# 24V_Regulators.net
KiCad netlist of a schematic drawn in Altium Designer
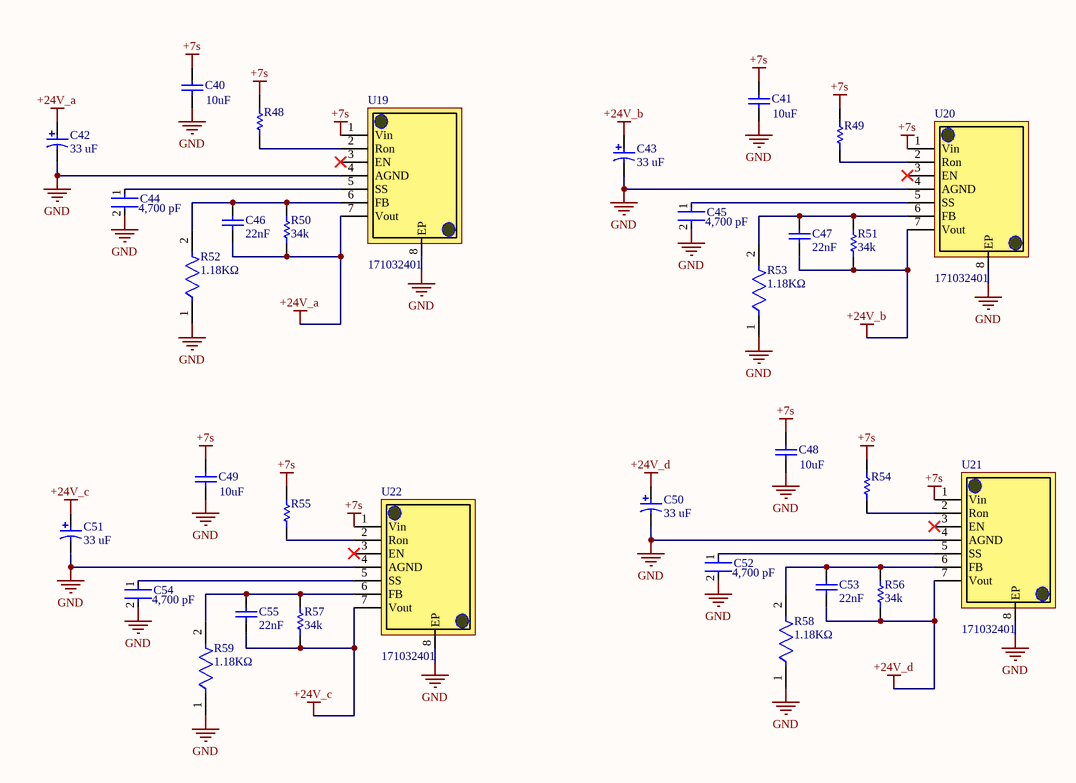
[diagram p0: 24V Regulators.SchDoc]

(export (version "E")
  (design (tool "Eeschema 10.0.6"))
  (components
    (comp (ref "C40")
      (value "10uF")
      (footprint "C1206")
      (description "Capacitor (Semiconductor SIM Model)")
      (fields (field (name "Comment") "Cap Semi") (field (name "PUBLISHER") "Altium Limited"))
      (libsource (lib "Miscellaneous Devices") (part "Cap Semi"))
    )
    (comp (ref "C41")
      (value "10uF")
      (footprint "C1206")
      (description "Capacitor (Semiconductor SIM Model)")
      (fields (field (name "Comment") "Cap Semi") (field (name "PUBLISHER") "Altium Limited"))
      (libsource (lib "Miscellaneous Devices") (part "Cap Semi"))
    )
    (comp (ref "C42")
      (value "UUD1V330MCL1GS")
      (footprint "NIC-CAPA2-6.3X5.8_V")
      (fields (field (name "MANUFACTURER") "Nichicon") (field (name "RATED CAPACITANCE") "33 uF"))
      (libsource (lib "Altium Content Vault") (part "NIC-CAP-P-2"))
    )
    (comp (ref "C43")
      (value "UUD1V330MCL1GS")
      (footprint "NIC-CAPA2-6.3X5.8_V")
      (fields (field (name "MANUFACTURER") "Nichicon") (field (name "RATED CAPACITANCE") "33 uF"))
      (libsource (lib "Altium Content Vault") (part "NIC-CAP-P-2"))
    )
    (comp (ref "C44")
      (value "C0805C472K5RACTU")
      (footprint "FP-C0805C-DN-MFG")
      (description "CAP CER 4700PF 50V X7R 0805")
      (fields
        (field (name "TOLERANCE") "0.1")
        (field (name "MANUFACTURER") "KEMET")
        (field (name "CAPACITANCE") "4,700 pF")
      )
      (libsource (lib "Altium Content Vault") (part "b4654b650e69147ec39a6b967a45e02"))
    )
    (comp (ref "C45")
      (value "C0805C472K5RACTU")
      (footprint "FP-C0805C-DN-MFG")
      (description "CAP CER 4700PF 50V X7R 0805")
      (fields
        (field (name "TOLERANCE") "0.1")
        (field (name "MANUFACTURER") "KEMET")
        (field (name "CAPACITANCE") "4,700 pF")
      )
      (libsource (lib "Altium Content Vault") (part "b4654b650e69147ec39a6b967a45e02"))
    )
    (comp (ref "C46")
      (value "22nF")
      (footprint "CAPC2013X145X50NL20T25")
      (fields (field (name "PART NUMBER") "C0805C223K1RACAUTO") (field (name "MANUFACTURER") "Kemet"))
      (libsource (lib "Altium Content Vault") (part "CAP"))
    )
    (comp (ref "C47")
      (value "22nF")
      (footprint "CAPC2013X145X50NL20T25")
      (fields (field (name "PART NUMBER") "C0805C223K1RACAUTO") (field (name "MANUFACTURER") "Kemet"))
      (libsource (lib "Altium Content Vault") (part "CAP"))
    )
    (comp (ref "C48")
      (value "10uF")
      (footprint "C1206")
      (description "Capacitor (Semiconductor SIM Model)")
      (fields (field (name "Comment") "Cap Semi") (field (name "PUBLISHER") "Altium Limited"))
      (libsource (lib "Miscellaneous Devices") (part "Cap Semi"))
    )
    (comp (ref "C49")
      (value "10uF")
      (footprint "C1206")
      (description "Capacitor (Semiconductor SIM Model)")
      (fields (field (name "Comment") "Cap Semi") (field (name "PUBLISHER") "Altium Limited"))
      (libsource (lib "Miscellaneous Devices") (part "Cap Semi"))
    )
    (comp (ref "C50")
      (value "UUD1V330MCL1GS")
      (footprint "NIC-CAPA2-6.3X5.8_V")
      (fields (field (name "MANUFACTURER") "Nichicon") (field (name "RATED CAPACITANCE") "33 uF"))
      (libsource (lib "Altium Content Vault") (part "NIC-CAP-P-2"))
    )
    (comp (ref "C51")
      (value "UUD1V330MCL1GS")
      (footprint "NIC-CAPA2-6.3X5.8_V")
      (fields (field (name "MANUFACTURER") "Nichicon") (field (name "RATED CAPACITANCE") "33 uF"))
      (libsource (lib "Altium Content Vault") (part "NIC-CAP-P-2"))
    )
    (comp (ref "C52")
      (value "C0805C472K5RACTU")
      (footprint "FP-C0805C-DN-MFG")
      (description "CAP CER 4700PF 50V X7R 0805")
      (fields
        (field (name "TOLERANCE") "0.1")
        (field (name "MANUFACTURER") "KEMET")
        (field (name "CAPACITANCE") "4,700 pF")
      )
      (libsource (lib "Altium Content Vault") (part "b4654b650e69147ec39a6b967a45e02"))
    )
    (comp (ref "C53")
      (value "22nF")
      (footprint "CAPC2013X145X50NL20T25")
      (fields (field (name "PART NUMBER") "C0805C223K1RACAUTO") (field (name "MANUFACTURER") "Kemet"))
      (libsource (lib "Altium Content Vault") (part "CAP"))
    )
    (comp (ref "C54")
      (value "C0805C472K5RACTU")
      (footprint "FP-C0805C-DN-MFG")
      (description "CAP CER 4700PF 50V X7R 0805")
      (fields
        (field (name "TOLERANCE") "0.1")
        (field (name "MANUFACTURER") "KEMET")
        (field (name "CAPACITANCE") "4,700 pF")
      )
      (libsource (lib "Altium Content Vault") (part "b4654b650e69147ec39a6b967a45e02"))
    )
    (comp (ref "C55")
      (value "22nF")
      (footprint "CAPC2013X145X50NL20T25")
      (fields (field (name "PART NUMBER") "C0805C223K1RACAUTO") (field (name "MANUFACTURER") "Kemet"))
      (libsource (lib "Altium Content Vault") (part "CAP"))
    )
    (comp (ref "R48")
      (value "RC0805FR-07499KL")
      (footprint "RESC2013X60X35LL10T20")
      (fields (field (name "MANUFACTURER") "Yageo"))
      (libsource (lib "Altium Content Vault") (part "RES"))
    )
    (comp (ref "R49")
      (value "RC0805FR-07499KL")
      (footprint "RESC2013X60X35LL10T20")
      (fields (field (name "MANUFACTURER") "Yageo"))
      (libsource (lib "Altium Content Vault") (part "RES"))
    )
    (comp (ref "R50")
      (value "34k")
      (footprint "RESC2013X60X40ML20T25")
      (fields (field (name "MANUFACTURER") "Panasonic") (field (name "PART NUMBER") "ERA6AEB3402V"))
      (libsource (lib "Altium Content Vault") (part "RES"))
    )
    (comp (ref "R51")
      (value "34k")
      (footprint "RESC2013X60X40ML20T25")
      (fields (field (name "MANUFACTURER") "Panasonic") (field (name "PART NUMBER") "ERA6AEB3402V"))
      (libsource (lib "Altium Content Vault") (part "RES"))
    )
    (comp (ref "R52")
      (value "1.18KΩ")
      (footprint "FP-RT0805-MFG")
      (description "RES SMD 1.18K OHM 0.1% 1/8W 0805")
      (fields
        (field (name "MANUFACTURER PART NUMBER") "RT0805BRE071K18L")
        (field (name "MANUFACTURER") "Yageo")
      )
      (libsource (lib "Altium Content Vault") (part "1029c3af85768c4190bb7ad29bc67b5"))
    )
    (comp (ref "R53")
      (value "1.18KΩ")
      (footprint "FP-RT0805-MFG")
      (description "RES SMD 1.18K OHM 0.1% 1/8W 0805")
      (fields
        (field (name "MANUFACTURER PART NUMBER") "RT0805BRE071K18L")
        (field (name "MANUFACTURER") "Yageo")
      )
      (libsource (lib "Altium Content Vault") (part "1029c3af85768c4190bb7ad29bc67b5"))
    )
    (comp (ref "R54")
      (value "RC0805FR-07499KL")
      (footprint "RESC2013X60X35LL10T20")
      (fields (field (name "MANUFACTURER") "Yageo"))
      (libsource (lib "Altium Content Vault") (part "RES"))
    )
    (comp (ref "R55")
      (value "RC0805FR-07499KL")
      (footprint "RESC2013X60X35LL10T20")
      (fields (field (name "MANUFACTURER") "Yageo"))
      (libsource (lib "Altium Content Vault") (part "RES"))
    )
    (comp (ref "R56")
      (value "34k")
      (footprint "RESC2013X60X40ML20T25")
      (fields (field (name "MANUFACTURER") "Panasonic") (field (name "PART NUMBER") "ERA6AEB3402V"))
      (libsource (lib "Altium Content Vault") (part "RES"))
    )
    (comp (ref "R57")
      (value "34k")
      (footprint "RESC2013X60X40ML20T25")
      (fields (field (name "MANUFACTURER") "Panasonic") (field (name "PART NUMBER") "ERA6AEB3402V"))
      (libsource (lib "Altium Content Vault") (part "RES"))
    )
    (comp (ref "R58")
      (value "1.18KΩ")
      (footprint "FP-RT0805-MFG")
      (description "RES SMD 1.18K OHM 0.1% 1/8W 0805")
      (fields
        (field (name "MANUFACTURER PART NUMBER") "RT0805BRE071K18L")
        (field (name "MANUFACTURER") "Yageo")
      )
      (libsource (lib "Altium Content Vault") (part "1029c3af85768c4190bb7ad29bc67b5"))
    )
    (comp (ref "R59")
      (value "1.18KΩ")
      (footprint "FP-RT0805-MFG")
      (description "RES SMD 1.18K OHM 0.1% 1/8W 0805")
      (fields
        (field (name "MANUFACTURER PART NUMBER") "RT0805BRE071K18L")
        (field (name "MANUFACTURER") "Yageo")
      )
      (libsource (lib "Altium Content Vault") (part "1029c3af85768c4190bb7ad29bc67b5"))
    )
    (comp (ref "U19")
      (value "171032401")
      (footprint "7 PIN PFM")
      (description "MagI³C-VDRM Variable Step Down Regulator Module WE-VDRM , Ui=6-42V")
      (fields (field (name "MANUFACTURER") "Wuerth Elektronik"))
      (libsource (lib "Altium Content Vault") (part "WE-17101240X_171020601_171032401"))
    )
    (comp (ref "U20")
      (value "171032401")
      (footprint "7 PIN PFM")
      (description "MagI³C-VDRM Variable Step Down Regulator Module WE-VDRM , Ui=6-42V")
      (fields (field (name "MANUFACTURER") "Wuerth Elektronik"))
      (libsource (lib "Altium Content Vault") (part "WE-17101240X_171020601_171032401"))
    )
    (comp (ref "U21")
      (value "171032401")
      (footprint "7 PIN PFM")
      (description "MagI³C-VDRM Variable Step Down Regulator Module WE-VDRM , Ui=6-42V")
      (fields (field (name "MANUFACTURER") "Wuerth Elektronik"))
      (libsource (lib "Altium Content Vault") (part "WE-17101240X_171020601_171032401"))
    )
    (comp (ref "U22")
      (value "171032401")
      (footprint "7 PIN PFM")
      (description "MagI³C-VDRM Variable Step Down Regulator Module WE-VDRM , Ui=6-42V")
      (fields (field (name "MANUFACTURER") "Wuerth Elektronik"))
      (libsource (lib "Altium Content Vault") (part "WE-17101240X_171020601_171032401"))
    )
  )
  (nets
    (net (code "1") (name "+7s") (class "Default")
      (node (ref "C40") (pin "1") (pinfunction "1_1") (pintype "passive"))
      (node (ref "C41") (pin "1") (pinfunction "1_1") (pintype "passive"))
      (node (ref "C48") (pin "1") (pinfunction "1_1") (pintype "passive"))
      (node (ref "C49") (pin "1") (pinfunction "1_1") (pintype "passive"))
      (node (ref "R48") (pin "1") (pinfunction "1_1") (pintype "passive"))
      (node (ref "R49") (pin "1") (pinfunction "1_1") (pintype "passive"))
      (node (ref "R54") (pin "1") (pinfunction "1_1") (pintype "passive"))
      (node (ref "R55") (pin "1") (pinfunction "1_1") (pintype "passive"))
      (node (ref "U19") (pin "1") (pinfunction "Vin_1") (pintype "passive"))
      (node (ref "U20") (pin "1") (pinfunction "Vin_1") (pintype "passive"))
      (node (ref "U21") (pin "1") (pinfunction "Vin_1") (pintype "passive"))
      (node (ref "U22") (pin "1") (pinfunction "Vin_1") (pintype "passive"))
    )
    (net (code "2") (name "+24V_a") (class "Default")
      (node (ref "C42") (pin "1") (pinfunction "1_1") (pintype "passive"))
      (node (ref "C46") (pin "1") (pinfunction "1_1") (pintype "passive"))
      (node (ref "R50") (pin "1") (pinfunction "1_1") (pintype "passive"))
      (node (ref "U19") (pin "7") (pinfunction "Vout_7") (pintype "power_in"))
    )
    (net (code "3") (name "+24V_b") (class "Default")
      (node (ref "C43") (pin "1") (pinfunction "1_1") (pintype "passive"))
      (node (ref "C47") (pin "1") (pinfunction "1_1") (pintype "passive"))
      (node (ref "R51") (pin "1") (pinfunction "1_1") (pintype "passive"))
      (node (ref "U20") (pin "7") (pinfunction "Vout_7") (pintype "power_in"))
    )
    (net (code "4") (name "+24V_c") (class "Default")
      (node (ref "C51") (pin "1") (pinfunction "1_1") (pintype "passive"))
      (node (ref "C55") (pin "1") (pinfunction "1_1") (pintype "passive"))
      (node (ref "R57") (pin "1") (pinfunction "1_1") (pintype "passive"))
      (node (ref "U22") (pin "7") (pinfunction "Vout_7") (pintype "power_in"))
    )
    (net (code "5") (name "+24V_d") (class "Default")
      (node (ref "C50") (pin "1") (pinfunction "1_1") (pintype "passive"))
      (node (ref "C53") (pin "1") (pinfunction "1_1") (pintype "passive"))
      (node (ref "R56") (pin "1") (pinfunction "1_1") (pintype "passive"))
      (node (ref "U21") (pin "7") (pinfunction "Vout_7") (pintype "power_in"))
    )
    (net (code "6") (name "GND") (class "Default")
      (node (ref "C40") (pin "2") (pinfunction "2_2") (pintype "passive"))
      (node (ref "C41") (pin "2") (pinfunction "2_2") (pintype "passive"))
      (node (ref "C42") (pin "2") (pinfunction "2_2") (pintype "passive"))
      (node (ref "C43") (pin "2") (pinfunction "2_2") (pintype "passive"))
      (node (ref "C44") (pin "2") (pinfunction "2_2") (pintype "passive"))
      (node (ref "C45") (pin "2") (pinfunction "2_2") (pintype "passive"))
      (node (ref "C48") (pin "2") (pinfunction "2_2") (pintype "passive"))
      (node (ref "C49") (pin "2") (pinfunction "2_2") (pintype "passive"))
      (node (ref "C50") (pin "2") (pinfunction "2_2") (pintype "passive"))
      (node (ref "C51") (pin "2") (pinfunction "2_2") (pintype "passive"))
      (node (ref "C52") (pin "2") (pinfunction "2_2") (pintype "passive"))
      (node (ref "C54") (pin "2") (pinfunction "2_2") (pintype "passive"))
      (node (ref "R52") (pin "1") (pinfunction "1_1") (pintype "passive"))
      (node (ref "R53") (pin "1") (pinfunction "1_1") (pintype "passive"))
      (node (ref "R58") (pin "1") (pinfunction "1_1") (pintype "passive"))
      (node (ref "R59") (pin "1") (pinfunction "1_1") (pintype "passive"))
      (node (ref "U19") (pin "4") (pinfunction "AGND_4") (pintype "passive"))
      (node (ref "U19") (pin "8") (pinfunction "EP_8") (pintype "passive"))
      (node (ref "U20") (pin "4") (pinfunction "AGND_4") (pintype "passive"))
      (node (ref "U20") (pin "8") (pinfunction "EP_8") (pintype "passive"))
      (node (ref "U21") (pin "4") (pinfunction "AGND_4") (pintype "passive"))
      (node (ref "U21") (pin "8") (pinfunction "EP_8") (pintype "passive"))
      (node (ref "U22") (pin "4") (pinfunction "AGND_4") (pintype "passive"))
      (node (ref "U22") (pin "8") (pinfunction "EP_8") (pintype "passive"))
    )
    (net (code "7") (name "Net-(U19-FB)") (class "Default")
      (node (ref "C46") (pin "2") (pinfunction "2_2") (pintype "passive"))
      (node (ref "R50") (pin "2") (pinfunction "2_2") (pintype "passive"))
      (node (ref "R52") (pin "2") (pinfunction "2_2") (pintype "passive"))
      (node (ref "U19") (pin "6") (pinfunction "FB_6") (pintype "passive"))
    )
    (net (code "8") (name "Net-(U19-Ron)") (class "Default")
      (node (ref "R48") (pin "2") (pinfunction "2_2") (pintype "passive"))
      (node (ref "U19") (pin "2") (pinfunction "Ron_2") (pintype "passive"))
    )
    (net (code "9") (name "Net-(U19-SS)") (class "Default")
      (node (ref "C44") (pin "1") (pinfunction "1_1") (pintype "passive"))
      (node (ref "U19") (pin "5") (pinfunction "SS_5") (pintype "passive"))
    )
    (net (code "10") (name "Net-(U20-FB)") (class "Default")
      (node (ref "C47") (pin "2") (pinfunction "2_2") (pintype "passive"))
      (node (ref "R51") (pin "2") (pinfunction "2_2") (pintype "passive"))
      (node (ref "R53") (pin "2") (pinfunction "2_2") (pintype "passive"))
      (node (ref "U20") (pin "6") (pinfunction "FB_6") (pintype "passive"))
    )
    (net (code "11") (name "Net-(U20-Ron)") (class "Default")
      (node (ref "R49") (pin "2") (pinfunction "2_2") (pintype "passive"))
      (node (ref "U20") (pin "2") (pinfunction "Ron_2") (pintype "passive"))
    )
    (net (code "12") (name "Net-(U20-SS)") (class "Default")
      (node (ref "C45") (pin "1") (pinfunction "1_1") (pintype "passive"))
      (node (ref "U20") (pin "5") (pinfunction "SS_5") (pintype "passive"))
    )
    (net (code "13") (name "Net-(U21-FB)") (class "Default")
      (node (ref "C53") (pin "2") (pinfunction "2_2") (pintype "passive"))
      (node (ref "R56") (pin "2") (pinfunction "2_2") (pintype "passive"))
      (node (ref "R58") (pin "2") (pinfunction "2_2") (pintype "passive"))
      (node (ref "U21") (pin "6") (pinfunction "FB_6") (pintype "passive"))
    )
    (net (code "14") (name "Net-(U21-Ron)") (class "Default")
      (node (ref "R54") (pin "2") (pinfunction "2_2") (pintype "passive"))
      (node (ref "U21") (pin "2") (pinfunction "Ron_2") (pintype "passive"))
    )
    (net (code "15") (name "Net-(U21-SS)") (class "Default")
      (node (ref "C52") (pin "1") (pinfunction "1_1") (pintype "passive"))
      (node (ref "U21") (pin "5") (pinfunction "SS_5") (pintype "passive"))
    )
    (net (code "16") (name "Net-(U22-FB)") (class "Default")
      (node (ref "C55") (pin "2") (pinfunction "2_2") (pintype "passive"))
      (node (ref "R57") (pin "2") (pinfunction "2_2") (pintype "passive"))
      (node (ref "R59") (pin "2") (pinfunction "2_2") (pintype "passive"))
      (node (ref "U22") (pin "6") (pinfunction "FB_6") (pintype "passive"))
    )
    (net (code "17") (name "Net-(U22-Ron)") (class "Default")
      (node (ref "R55") (pin "2") (pinfunction "2_2") (pintype "passive"))
      (node (ref "U22") (pin "2") (pinfunction "Ron_2") (pintype "passive"))
    )
    (net (code "18") (name "Net-(U22-SS)") (class "Default")
      (node (ref "C54") (pin "1") (pinfunction "1_1") (pintype "passive"))
      (node (ref "U22") (pin "5") (pinfunction "SS_5") (pintype "passive"))
    )
    (net (code "19") (name "unconnected-(U19-EN-Pad3)") (class "Default")
      (node (ref "U19") (pin "3") (pinfunction "EN_3") (pintype "passive+no_connect"))
    )
    (net (code "20") (name "unconnected-(U20-EN-Pad3)") (class "Default")
      (node (ref "U20") (pin "3") (pinfunction "EN_3") (pintype "passive+no_connect"))
    )
    (net (code "21") (name "unconnected-(U21-EN-Pad3)") (class "Default")
      (node (ref "U21") (pin "3") (pinfunction "EN_3") (pintype "passive+no_connect"))
    )
    (net (code "22") (name "unconnected-(U22-EN-Pad3)") (class "Default")
      (node (ref "U22") (pin "3") (pinfunction "EN_3") (pintype "passive+no_connect"))
    )
  )
)
